# Analog_Multiplier.net
KiCad netlist of a schematic drawn in Altium Designer
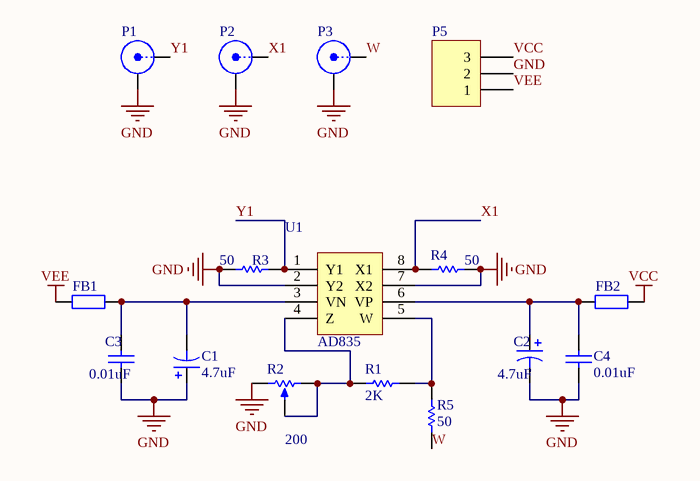
[diagram p0: Analog_Multiplier.SchDoc]

(export (version "E")
  (design (tool "Eeschema 10.0.6"))
  (components
    (comp (ref "C1")
      (value "4.7uF")
      (footprint "0805")
      (description "Polarized Capacitor (Surface Mount)")
      (fields (field (name "Comment") "Cap Pol3") (field (name "PUBLISHER") "Altium Limited"))
      (libsource (lib "Miscellaneous Devices") (part "Cap Pol3"))
    )
    (comp (ref "C2")
      (value "4.7uF")
      (footprint "0805")
      (description "Polarized Capacitor (Surface Mount)")
      (fields (field (name "Comment") "Cap Pol3") (field (name "PUBLISHER") "Altium Limited"))
      (libsource (lib "Miscellaneous Devices") (part "Cap Pol3"))
    )
    (comp (ref "C3")
      (value "0.01uF")
      (footprint "0805")
      (description "Capacitor (Semiconductor SIM Model)")
      (fields (field (name "Comment") "Cap Semi") (field (name "PUBLISHER") "Altium Limited"))
      (libsource (lib "Miscellaneous Devices") (part "Cap Semi"))
    )
    (comp (ref "C4")
      (value "0.01uF")
      (footprint "0805")
      (description "Capacitor (Semiconductor SIM Model)")
      (fields (field (name "Comment") "Cap Semi") (field (name "PUBLISHER") "Altium Limited"))
      (libsource (lib "Miscellaneous Devices") (part "Cap Semi"))
    )
    (comp (ref "FB1")
      (value "Res2")
      (footprint "1206")
      (description "Resistor")
      (fields (field (name "PUBLISHER") "Altium Limited"))
      (libsource (lib "Miscellaneous Devices") (part "Res2"))
    )
    (comp (ref "FB2")
      (value "Res2")
      (footprint "1206")
      (description "Resistor")
      (fields (field (name "PUBLISHER") "Altium Limited"))
      (libsource (lib "Miscellaneous Devices") (part "Res2"))
    )
    (comp (ref "P1")
      (value "SMB")
      (footprint "SMB_V-RJ45")
      (description "SMB Straight Connector")
      (fields (field (name "PUBLISHER") "Altium Limited"))
      (libsource (lib "Miscellaneous Connectors") (part "SMB"))
    )
    (comp (ref "P2")
      (value "SMB")
      (footprint "SMB_V-RJ45")
      (description "SMB Straight Connector")
      (fields (field (name "PUBLISHER") "Altium Limited"))
      (libsource (lib "Miscellaneous Connectors") (part "SMB"))
    )
    (comp (ref "P3")
      (value "SMB")
      (footprint "SMB_V-RJ45")
      (description "SMB Straight Connector")
      (fields (field (name "PUBLISHER") "Altium Limited"))
      (libsource (lib "Miscellaneous Connectors") (part "SMB"))
    )
    (comp (ref "P5")
      (value "Header 3")
      (footprint "HDR1X3")
      (description "Header, 3-Pin")
      (fields (field (name "PUBLISHER") "Altium Limited"))
      (libsource (lib "Miscellaneous Connectors") (part "Header 3"))
    )
    (comp (ref "R1")
      (value "2K")
      (footprint "AXIAL-0.3")
      (description "Resistor")
      (fields (field (name "Comment") "Res1") (field (name "PUBLISHER") "Altium Limited"))
      (libsource (lib "Miscellaneous Devices") (part "Res1"))
    )
    (comp (ref "R2")
      (value "200")
      (footprint "VR5")
      (description "Potentiometer")
      (fields (field (name "Comment") "RPot") (field (name "PUBLISHER") "Altium Limited"))
      (libsource (lib "Miscellaneous Devices") (part "RPot"))
    )
    (comp (ref "R3")
      (value "50")
      (footprint "0805")
      (description "Resistor")
      (fields (field (name "Comment") "Res1") (field (name "PUBLISHER") "Altium Limited"))
      (libsource (lib "Miscellaneous Devices") (part "Res1"))
    )
    (comp (ref "R4")
      (value "50")
      (footprint "0805")
      (description "Resistor")
      (fields (field (name "Comment") "Res1") (field (name "PUBLISHER") "Altium Limited"))
      (libsource (lib "Miscellaneous Devices") (part "Res1"))
    )
    (comp (ref "R5")
      (value "50")
      (footprint "0805")
      (description "Resistor")
      (fields (field (name "Comment") "Res1") (field (name "PUBLISHER") "Altium Limited"))
      (libsource (lib "Miscellaneous Devices") (part "Res1"))
    )
    (comp (ref "U1")
      (value "AD835")
      (footprint "AD835_SOP8 - duplicate1")
      (libsource (lib "AD835") (part "Component_1"))
    )
  )
  (nets
    (net (code "1") (name "/W") (class "Default")
      (node (ref "P3") (pin "1") (pinfunction "X_1") (pintype "passive"))
      (node (ref "R5") (pin "1") (pinfunction "1_1") (pintype "passive"))
    )
    (net (code "2") (name "/X1") (class "Default")
      (node (ref "P2") (pin "1") (pinfunction "X_1") (pintype "passive"))
      (node (ref "R4") (pin "2") (pinfunction "2_2") (pintype "passive"))
      (node (ref "U1") (pin "8") (pinfunction "X1_8") (pintype "open_emitter"))
    )
    (net (code "3") (name "/Y1") (class "Default")
      (node (ref "P1") (pin "1") (pinfunction "X_1") (pintype "passive"))
      (node (ref "R3") (pin "1") (pinfunction "1_1") (pintype "passive"))
      (node (ref "U1") (pin "1") (pinfunction "Y1_1") (pintype "open_emitter"))
    )
    (net (code "4") (name "GND") (class "Default")
      (node (ref "C1") (pin "1") (pinfunction "1_1") (pintype "passive"))
      (node (ref "C2") (pin "2") (pinfunction "2_2") (pintype "passive"))
      (node (ref "C3") (pin "2") (pinfunction "2_2") (pintype "passive"))
      (node (ref "C4") (pin "2") (pinfunction "2_2") (pintype "passive"))
      (node (ref "P1") (pin "2") (pinfunction "Y_2") (pintype "passive"))
      (node (ref "P2") (pin "2") (pinfunction "Y_2") (pintype "passive"))
      (node (ref "P3") (pin "2") (pinfunction "Y_2") (pintype "passive"))
      (node (ref "P5") (pin "2") (pinfunction "2_2") (pintype "passive"))
      (node (ref "R2") (pin "1") (pinfunction "TOP_1") (pintype "passive"))
      (node (ref "R3") (pin "2") (pinfunction "2_2") (pintype "passive"))
      (node (ref "R4") (pin "1") (pinfunction "1_1") (pintype "passive"))
      (node (ref "U1") (pin "2") (pinfunction "Y2_2") (pintype "open_emitter"))
      (node (ref "U1") (pin "7") (pinfunction "X2_7") (pintype "open_emitter"))
    )
    (net (code "5") (name "Net-(R2-BOT)") (class "Default")
      (node (ref "R1") (pin "1") (pinfunction "1_1") (pintype "passive"))
      (node (ref "R2") (pin "2") (pinfunction "TAP_2") (pintype "passive"))
      (node (ref "R2") (pin "3") (pinfunction "BOT_3") (pintype "passive"))
      (node (ref "U1") (pin "4") (pinfunction "Z_4") (pintype "open_emitter"))
    )
    (net (code "6") (name "Net-(U1-VN)") (class "Default")
      (node (ref "C1") (pin "2") (pinfunction "2_2") (pintype "passive"))
      (node (ref "C3") (pin "1") (pinfunction "1_1") (pintype "passive"))
      (node (ref "FB1") (pin "1") (pinfunction "1_1") (pintype "passive"))
      (node (ref "U1") (pin "3") (pinfunction "VN_3") (pintype "open_emitter"))
    )
    (net (code "7") (name "Net-(U1-VP)") (class "Default")
      (node (ref "C2") (pin "1") (pinfunction "1_1") (pintype "passive"))
      (node (ref "C4") (pin "1") (pinfunction "1_1") (pintype "passive"))
      (node (ref "FB2") (pin "2") (pinfunction "2_2") (pintype "passive"))
      (node (ref "U1") (pin "6") (pinfunction "VP_6") (pintype "open_emitter"))
    )
    (net (code "8") (name "Net-(U1-W)") (class "Default")
      (node (ref "R1") (pin "2") (pinfunction "2_2") (pintype "passive"))
      (node (ref "R5") (pin "2") (pinfunction "2_2") (pintype "passive"))
      (node (ref "U1") (pin "5") (pinfunction "W_5") (pintype "open_emitter"))
    )
    (net (code "9") (name "VCC") (class "Default")
      (node (ref "FB2") (pin "1") (pinfunction "1_1") (pintype "passive"))
      (node (ref "P5") (pin "3") (pinfunction "3_3") (pintype "passive"))
    )
    (net (code "10") (name "VEE") (class "Default")
      (node (ref "FB1") (pin "2") (pinfunction "2_2") (pintype "passive"))
      (node (ref "P5") (pin "1") (pinfunction "1_1") (pintype "passive"))
    )
  )
)
